# bs_prod.net
KiCad netlist of a schematic drawn in EAGLE
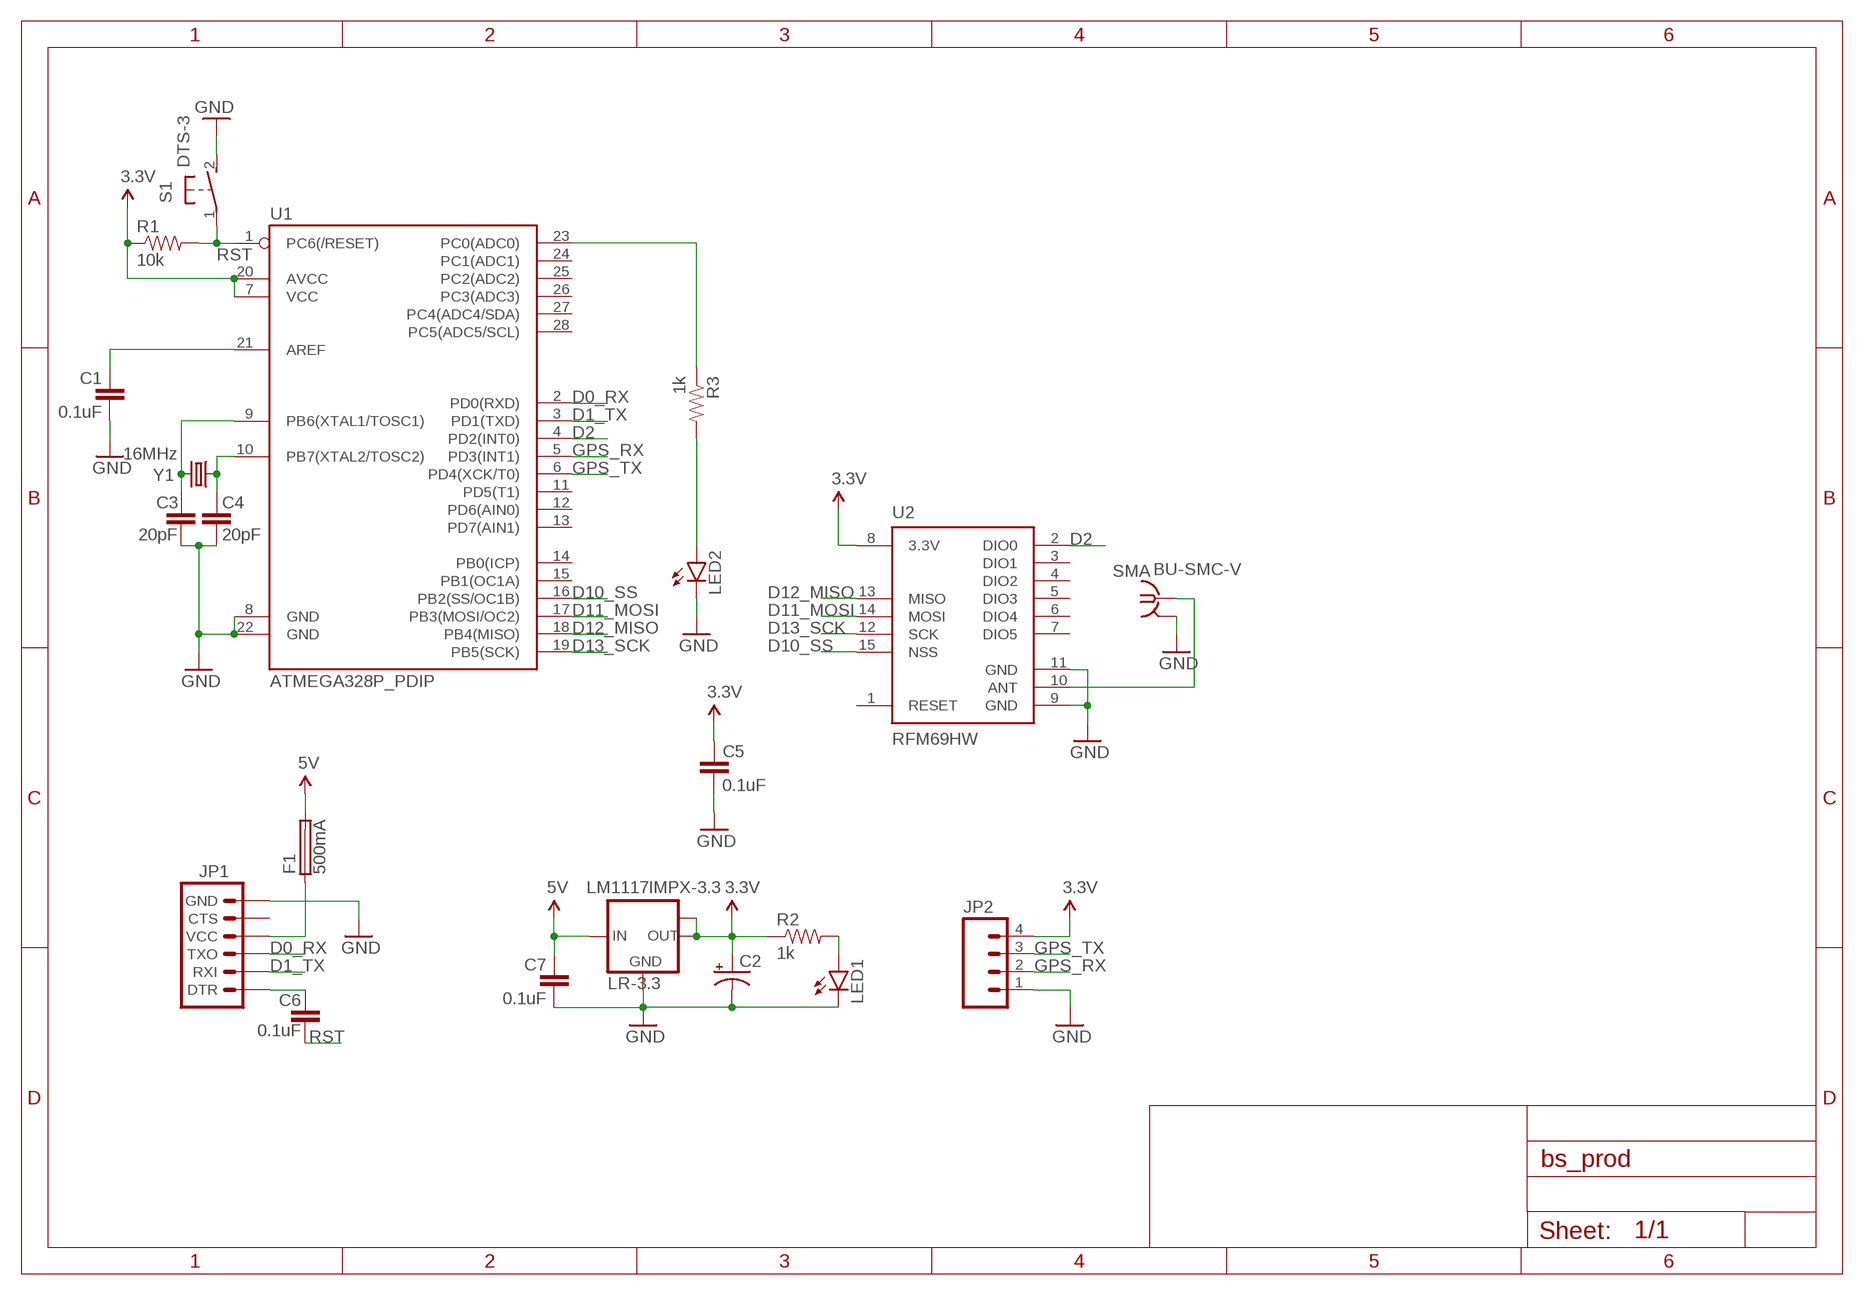
[diagram p0: schematic, sheet 1]

(export (version "E")
  (design (tool "Eeschema 10.0.6"))
  (components
    (comp (ref "C1")
      (value "0.1uF")
      (footprint "eagle-import:1206")
      (libsource (lib "eagle-import") (part "CAP1206"))
    )
    (comp (ref "C2")
      (value "CAP_POLC")
      (footprint "eagle-import:PANASONIC_C")
      (libsource (lib "eagle-import") (part "CAP_POLC"))
    )
    (comp (ref "C3")
      (value "20pF")
      (footprint "eagle-import:1206")
      (libsource (lib "eagle-import") (part "CAP1206"))
    )
    (comp (ref "C4")
      (value "20pF")
      (footprint "eagle-import:1206")
      (libsource (lib "eagle-import") (part "CAP1206"))
    )
    (comp (ref "C5")
      (value "0.1uF")
      (footprint "eagle-import:1206")
      (libsource (lib "eagle-import") (part "CAP1206"))
    )
    (comp (ref "C6")
      (value "0.1uF")
      (footprint "eagle-import:1206")
      (libsource (lib "eagle-import") (part "CAP1206"))
    )
    (comp (ref "C7")
      (value "0.1uF")
      (footprint "eagle-import:1206")
      (libsource (lib "eagle-import") (part "CAP1206"))
    )
    (comp (ref "F1")
      (value "500mA")
      (footprint "eagle-import:TE5")
      (libsource (lib "eagle-import") (part "TE5"))
    )
    (comp (ref "JP1")
      (value "ARDUINO_SERIAL_PROGRAMPTH")
      (footprint "eagle-import:1X06")
      (libsource (lib "eagle-import") (part "ARDUINO_SERIAL_PROGRAMPTH"))
    )
    (comp (ref "JP2")
      (value "M04PTH")
      (footprint "eagle-import:1X04")
      (libsource (lib "eagle-import") (part "M04PTH"))
    )
    (comp (ref "LED1")
      (value "LED1206")
      (footprint "eagle-import:LED-1206")
      (libsource (lib "eagle-import") (part "LED1206"))
    )
    (comp (ref "LED2")
      (value "LED1206")
      (footprint "eagle-import:LED-1206")
      (libsource (lib "eagle-import") (part "LED1206"))
    )
    (comp (ref "LR-3.3")
      (value "LM1117IMPX-3.3")
      (footprint "eagle-import:SOT223")
      (libsource (lib "eagle-import") (part "LM1117IMPX-3.3"))
    )
    (comp (ref "R1")
      (value "10k")
      (footprint "eagle-import:1206")
      (libsource (lib "eagle-import") (part "RESISTOR1206"))
    )
    (comp (ref "R2")
      (value "1k")
      (footprint "eagle-import:1206")
      (libsource (lib "eagle-import") (part "RESISTOR1206"))
    )
    (comp (ref "R3")
      (value "1k")
      (footprint "eagle-import:1206")
      (libsource (lib "eagle-import") (part "RESISTOR1206"))
    )
    (comp (ref "S1")
      (value "DTS-3")
      (footprint "eagle-import:DTS-3")
      (libsource (lib "eagle-import") (part "DTS-3"))
    )
    (comp (ref "SMA")
      (value "BU-SMC-V")
      (footprint "eagle-import:BU-SMC-V")
      (libsource (lib "eagle-import") (part "BU-SMC-V"))
    )
    (comp (ref "U1")
      (value "ATMEGA328P_PDIP")
      (footprint "eagle-import:DIL28-3")
      (libsource (lib "eagle-import") (part "ATMEGA328P_PDIP"))
    )
    (comp (ref "U2")
      (value "RFM69HW")
      (footprint "eagle-import:RFM69W-XXXS2")
      (libsource (lib "eagle-import") (part "RFM69HW"))
    )
    (comp (ref "Y1")
      (value "16MHz")
      (footprint "eagle-import:HC49UP")
      (libsource (lib "eagle-import") (part "CRYSTALSMD"))
    )
  )
  (nets
    (net (code "1") (name "/D0_RX") (class "Default")
      (node (ref "JP1") (pin "3") (pinfunction "TXO_3") (pintype "passive"))
      (node (ref "U1") (pin "2") (pinfunction "PD0(RXD)_2") (pintype "bidirectional"))
    )
    (net (code "2") (name "/D1_TX") (class "Default")
      (node (ref "JP1") (pin "2") (pinfunction "RXI_2") (pintype "passive"))
      (node (ref "U1") (pin "3") (pinfunction "PD1(TXD)_3") (pintype "bidirectional"))
    )
    (net (code "3") (name "/D2") (class "Default")
      (node (ref "U1") (pin "4") (pinfunction "PD2(INT0)_4") (pintype "bidirectional"))
      (node (ref "U2") (pin "2") (pinfunction "DIO0_2") (pintype "bidirectional"))
    )
    (net (code "4") (name "/D10_SS") (class "Default")
      (node (ref "U1") (pin "16") (pinfunction "PB2(SS/OC1B)_16") (pintype "bidirectional"))
      (node (ref "U2") (pin "15") (pinfunction "NSS_15") (pintype "input"))
    )
    (net (code "5") (name "/D11_MOSI") (class "Default")
      (node (ref "U1") (pin "17") (pinfunction "PB3(MOSI/OC2)_17") (pintype "bidirectional"))
      (node (ref "U2") (pin "14") (pinfunction "MOSI_14") (pintype "input"))
    )
    (net (code "6") (name "/D12_MISO") (class "Default")
      (node (ref "U1") (pin "18") (pinfunction "PB4(MISO)_18") (pintype "bidirectional"))
      (node (ref "U2") (pin "13") (pinfunction "MISO_13") (pintype "bidirectional"))
    )
    (net (code "7") (name "/D13_SCK") (class "Default")
      (node (ref "U1") (pin "19") (pinfunction "PB5(SCK)_19") (pintype "bidirectional"))
      (node (ref "U2") (pin "12") (pinfunction "SCK_12") (pintype "input"))
    )
    (net (code "8") (name "/GPS_RX") (class "Default")
      (node (ref "JP2") (pin "2") (pinfunction "2_2") (pintype "passive"))
      (node (ref "U1") (pin "5") (pinfunction "PD3(INT1)_5") (pintype "bidirectional"))
    )
    (net (code "9") (name "/GPS_TX") (class "Default")
      (node (ref "JP2") (pin "3") (pinfunction "3_3") (pintype "passive"))
      (node (ref "U1") (pin "6") (pinfunction "PD4(XCK/T0)_6") (pintype "bidirectional"))
    )
    (net (code "10") (name "/RST") (class "Default")
      (node (ref "C6") (pin "2") (pinfunction "2_2") (pintype "passive"))
      (node (ref "R1") (pin "2") (pinfunction "2_2") (pintype "passive"))
      (node (ref "S1") (pin "1") (pinfunction "1_1") (pintype "passive"))
      (node (ref "U1") (pin "1") (pinfunction "PC6(/RESET)_1") (pintype "bidirectional"))
    )
    (net (code "11") (name "3.3V") (class "Default")
      (node (ref "C2") (pin "+") (pinfunction "+_+") (pintype "passive"))
      (node (ref "C5") (pin "1") (pinfunction "1_1") (pintype "passive"))
      (node (ref "JP2") (pin "4") (pinfunction "4_4") (pintype "passive"))
      (node (ref "LR-3.3") (pin "2") (pinfunction "OUT_2") (pintype "passive"))
      (node (ref "LR-3.3") (pin "TAB") (pinfunction "OUT1_TAB") (pintype "passive"))
      (node (ref "R1") (pin "1") (pinfunction "1_1") (pintype "passive"))
      (node (ref "R2") (pin "1") (pinfunction "1_1") (pintype "passive"))
      (node (ref "U1") (pin "20") (pinfunction "AVCC_20") (pintype "bidirectional"))
      (node (ref "U1") (pin "7") (pinfunction "VCC_7") (pintype "bidirectional"))
      (node (ref "U2") (pin "8") (pinfunction "3.3V_8") (pintype "power_in"))
    )
    (net (code "12") (name "5V") (class "Default")
      (node (ref "C7") (pin "1") (pinfunction "1_1") (pintype "passive"))
      (node (ref "F1") (pin "2") (pinfunction "2_2") (pintype "passive"))
      (node (ref "LR-3.3") (pin "3") (pinfunction "IN_3") (pintype "input"))
    )
    (net (code "13") (name "GND") (class "Default")
      (node (ref "C1") (pin "2") (pinfunction "2_2") (pintype "passive"))
      (node (ref "C2") (pin "-") (pinfunction "-_-") (pintype "passive"))
      (node (ref "C3") (pin "2") (pinfunction "2_2") (pintype "passive"))
      (node (ref "C4") (pin "2") (pinfunction "2_2") (pintype "passive"))
      (node (ref "C5") (pin "2") (pinfunction "2_2") (pintype "passive"))
      (node (ref "C7") (pin "2") (pinfunction "2_2") (pintype "passive"))
      (node (ref "JP1") (pin "6") (pinfunction "GND_6") (pintype "passive"))
      (node (ref "JP2") (pin "1") (pinfunction "1_1") (pintype "passive"))
      (node (ref "LED1") (pin "C") (pinfunction "C_C") (pintype "passive"))
      (node (ref "LED2") (pin "C") (pinfunction "C_C") (pintype "passive"))
      (node (ref "LR-3.3") (pin "1") (pinfunction "GND_1") (pintype "input"))
      (node (ref "S1") (pin "2") (pinfunction "2_2") (pintype "passive"))
      (node (ref "SMA") (pin "2") (pinfunction "2_2") (pintype "passive"))
      (node (ref "SMA") (pin "3") (pinfunction "2_3") (pintype "passive"))
      (node (ref "SMA") (pin "4") (pinfunction "2_4") (pintype "passive"))
      (node (ref "SMA") (pin "5") (pinfunction "2_5") (pintype "passive"))
      (node (ref "U1") (pin "22") (pinfunction "GND_22") (pintype "bidirectional"))
      (node (ref "U1") (pin "8") (pinfunction "GND_8") (pintype "bidirectional"))
      (node (ref "U2") (pin "11") (pinfunction "GND_11") (pintype "power_in"))
      (node (ref "U2") (pin "9") (pinfunction "GND_9") (pintype "power_in"))
    )
    (net (code "14") (name "Net-(JP1-DTR)") (class "Default")
      (node (ref "C6") (pin "1") (pinfunction "1_1") (pintype "passive"))
      (node (ref "JP1") (pin "1") (pinfunction "DTR_1") (pintype "passive"))
    )
    (net (code "15") (name "Net-(JP1-VCC)") (class "Default")
      (node (ref "F1") (pin "1") (pinfunction "1_1") (pintype "passive"))
      (node (ref "JP1") (pin "4") (pinfunction "VCC_4") (pintype "passive"))
    )
    (net (code "16") (name "Net-(LED1-PadA)") (class "Default")
      (node (ref "LED1") (pin "A") (pinfunction "A_A") (pintype "passive"))
      (node (ref "R2") (pin "2") (pinfunction "2_2") (pintype "passive"))
    )
    (net (code "17") (name "Net-(LED2-PadA)") (class "Default")
      (node (ref "LED2") (pin "A") (pinfunction "A_A") (pintype "passive"))
      (node (ref "R3") (pin "2") (pinfunction "2_2") (pintype "passive"))
    )
    (net (code "18") (name "Net-(U1-AREF)") (class "Default")
      (node (ref "C1") (pin "1") (pinfunction "1_1") (pintype "passive"))
      (node (ref "U1") (pin "21") (pinfunction "AREF_21") (pintype "bidirectional"))
    )
    (net (code "19") (name "Net-(U1-PB6(XTAL1{slash}TOSC1))") (class "Default")
      (node (ref "C3") (pin "1") (pinfunction "1_1") (pintype "passive"))
      (node (ref "U1") (pin "9") (pinfunction "PB6(XTAL1/TOSC1)_9") (pintype "bidirectional"))
      (node (ref "Y1") (pin "2") (pinfunction "2_2") (pintype "passive"))
    )
    (net (code "20") (name "Net-(U1-PB7(XTAL2{slash}TOSC2))") (class "Default")
      (node (ref "C4") (pin "1") (pinfunction "1_1") (pintype "passive"))
      (node (ref "U1") (pin "10") (pinfunction "PB7(XTAL2/TOSC2)_10") (pintype "bidirectional"))
      (node (ref "Y1") (pin "1") (pinfunction "1_1") (pintype "passive"))
    )
    (net (code "21") (name "Net-(U1-PC0(ADC0))") (class "Default")
      (node (ref "R3") (pin "1") (pinfunction "1_1") (pintype "passive"))
      (node (ref "U1") (pin "23") (pinfunction "PC0(ADC0)_23") (pintype "bidirectional"))
    )
    (net (code "22") (name "Net-(U2-ANT)") (class "Default")
      (node (ref "SMA") (pin "1") (pinfunction "1_1") (pintype "passive"))
      (node (ref "U2") (pin "10") (pinfunction "ANT_10") (pintype "passive"))
    )
    (net (code "23") (name "unconnected-(JP1-CTS-Pad5)") (class "Default")
      (node (ref "JP1") (pin "5") (pinfunction "CTS_5") (pintype "passive"))
    )
    (net (code "24") (name "unconnected-(U1-PB0(ICP)-Pad14)") (class "Default")
      (node (ref "U1") (pin "14") (pinfunction "PB0(ICP)_14") (pintype "bidirectional"))
    )
    (net (code "25") (name "unconnected-(U1-PB1(OC1A)-Pad15)") (class "Default")
      (node (ref "U1") (pin "15") (pinfunction "PB1(OC1A)_15") (pintype "bidirectional"))
    )
    (net (code "26") (name "unconnected-(U1-PC1(ADC1)-Pad24)") (class "Default")
      (node (ref "U1") (pin "24") (pinfunction "PC1(ADC1)_24") (pintype "bidirectional"))
    )
    (net (code "27") (name "unconnected-(U1-PC2(ADC2)-Pad25)") (class "Default")
      (node (ref "U1") (pin "25") (pinfunction "PC2(ADC2)_25") (pintype "bidirectional"))
    )
    (net (code "28") (name "unconnected-(U1-PC3(ADC3)-Pad26)") (class "Default")
      (node (ref "U1") (pin "26") (pinfunction "PC3(ADC3)_26") (pintype "bidirectional"))
    )
    (net (code "29") (name "unconnected-(U1-PC4(ADC4{slash}SDA)-Pad27)") (class "Default")
      (node (ref "U1") (pin "27") (pinfunction "PC4(ADC4/SDA)_27") (pintype "bidirectional"))
    )
    (net (code "30") (name "unconnected-(U1-PC5(ADC5{slash}SCL)-Pad28)") (class "Default")
      (node (ref "U1") (pin "28") (pinfunction "PC5(ADC5/SCL)_28") (pintype "bidirectional"))
    )
    (net (code "31") (name "unconnected-(U1-PD5(T1)-Pad11)") (class "Default")
      (node (ref "U1") (pin "11") (pinfunction "PD5(T1)_11") (pintype "bidirectional"))
    )
    (net (code "32") (name "unconnected-(U1-PD6(AIN0)-Pad12)") (class "Default")
      (node (ref "U1") (pin "12") (pinfunction "PD6(AIN0)_12") (pintype "bidirectional"))
    )
    (net (code "33") (name "unconnected-(U1-PD7(AIN1)-Pad13)") (class "Default")
      (node (ref "U1") (pin "13") (pinfunction "PD7(AIN1)_13") (pintype "bidirectional"))
    )
    (net (code "34") (name "unconnected-(U2-DIO1-Pad3)") (class "Default")
      (node (ref "U2") (pin "3") (pinfunction "DIO1_3") (pintype "bidirectional"))
    )
    (net (code "35") (name "unconnected-(U2-DIO2-Pad4)") (class "Default")
      (node (ref "U2") (pin "4") (pinfunction "DIO2_4") (pintype "bidirectional"))
    )
    (net (code "36") (name "unconnected-(U2-DIO3-Pad5)") (class "Default")
      (node (ref "U2") (pin "5") (pinfunction "DIO3_5") (pintype "bidirectional"))
    )
    (net (code "37") (name "unconnected-(U2-DIO4-Pad6)") (class "Default")
      (node (ref "U2") (pin "6") (pinfunction "DIO4_6") (pintype "bidirectional"))
    )
    (net (code "38") (name "unconnected-(U2-DIO5-Pad7)") (class "Default")
      (node (ref "U2") (pin "7") (pinfunction "DIO5_7") (pintype "bidirectional"))
    )
    (net (code "39") (name "unconnected-(U2-RESET-Pad1)") (class "Default")
      (node (ref "U2") (pin "1") (pinfunction "RESET_1") (pintype "input"))
    )
  )
)
